# design.net
KiCad netlist of a schematic drawn in Altium Designer
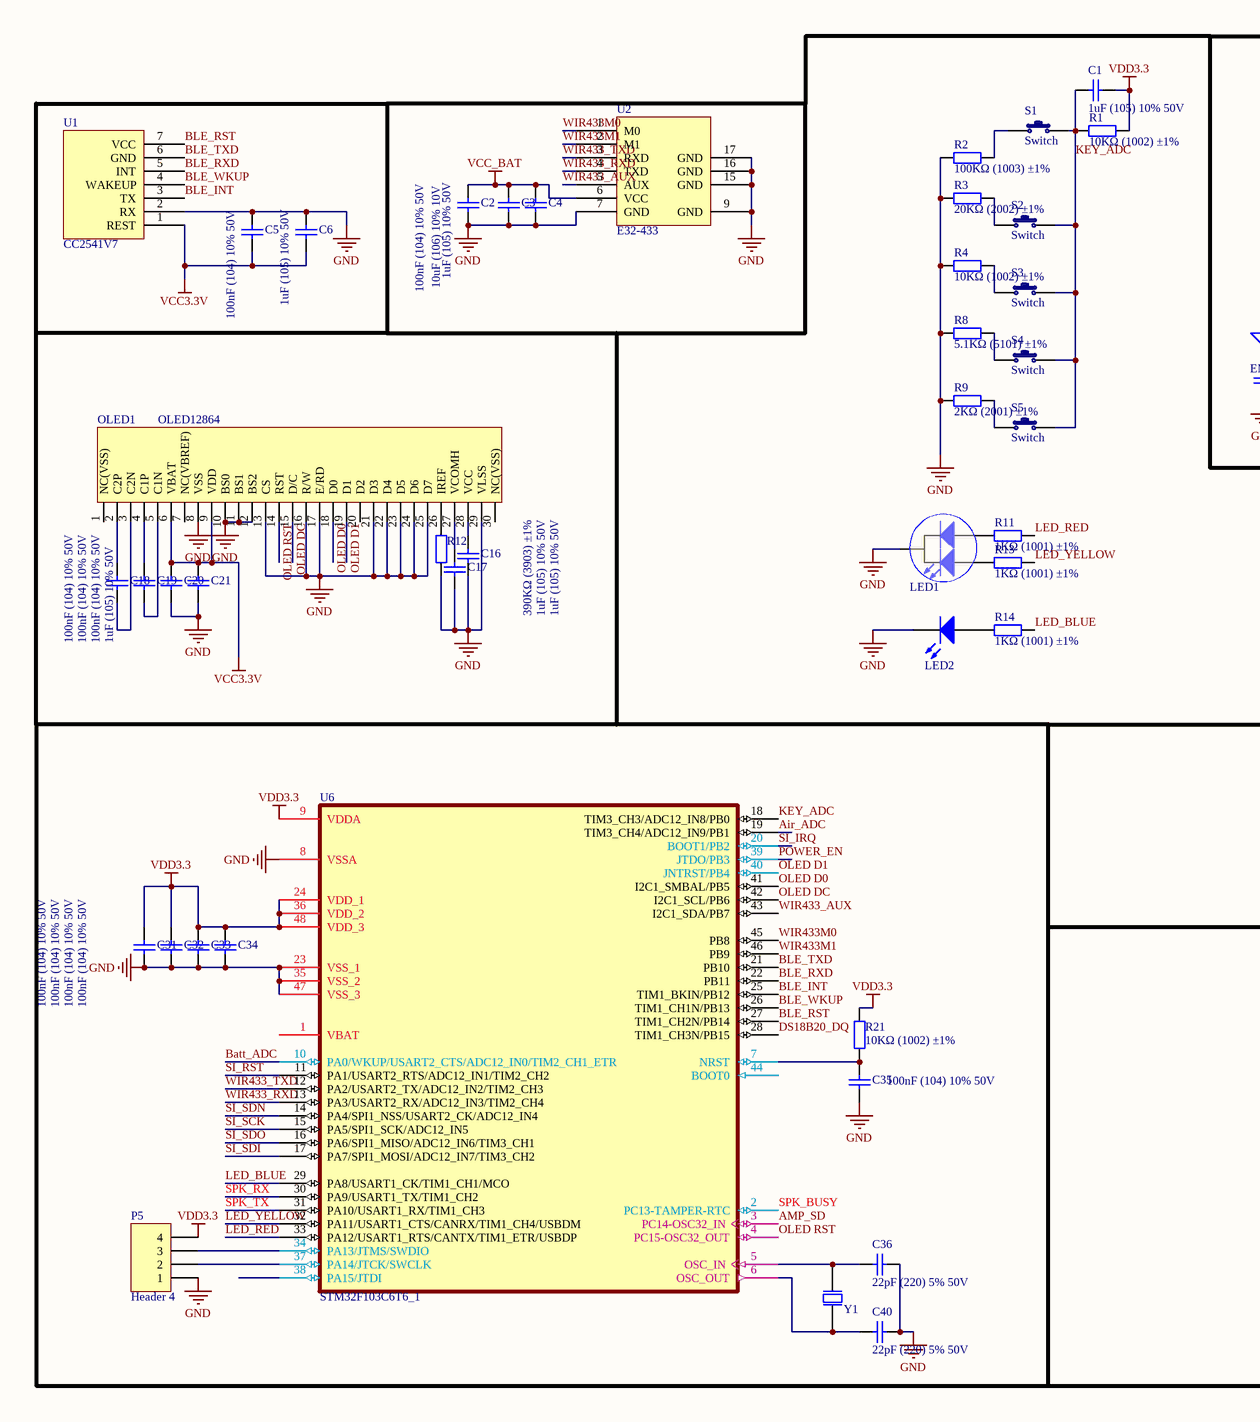
[diagram p0: 消防背表 备份.SchDoc, left]
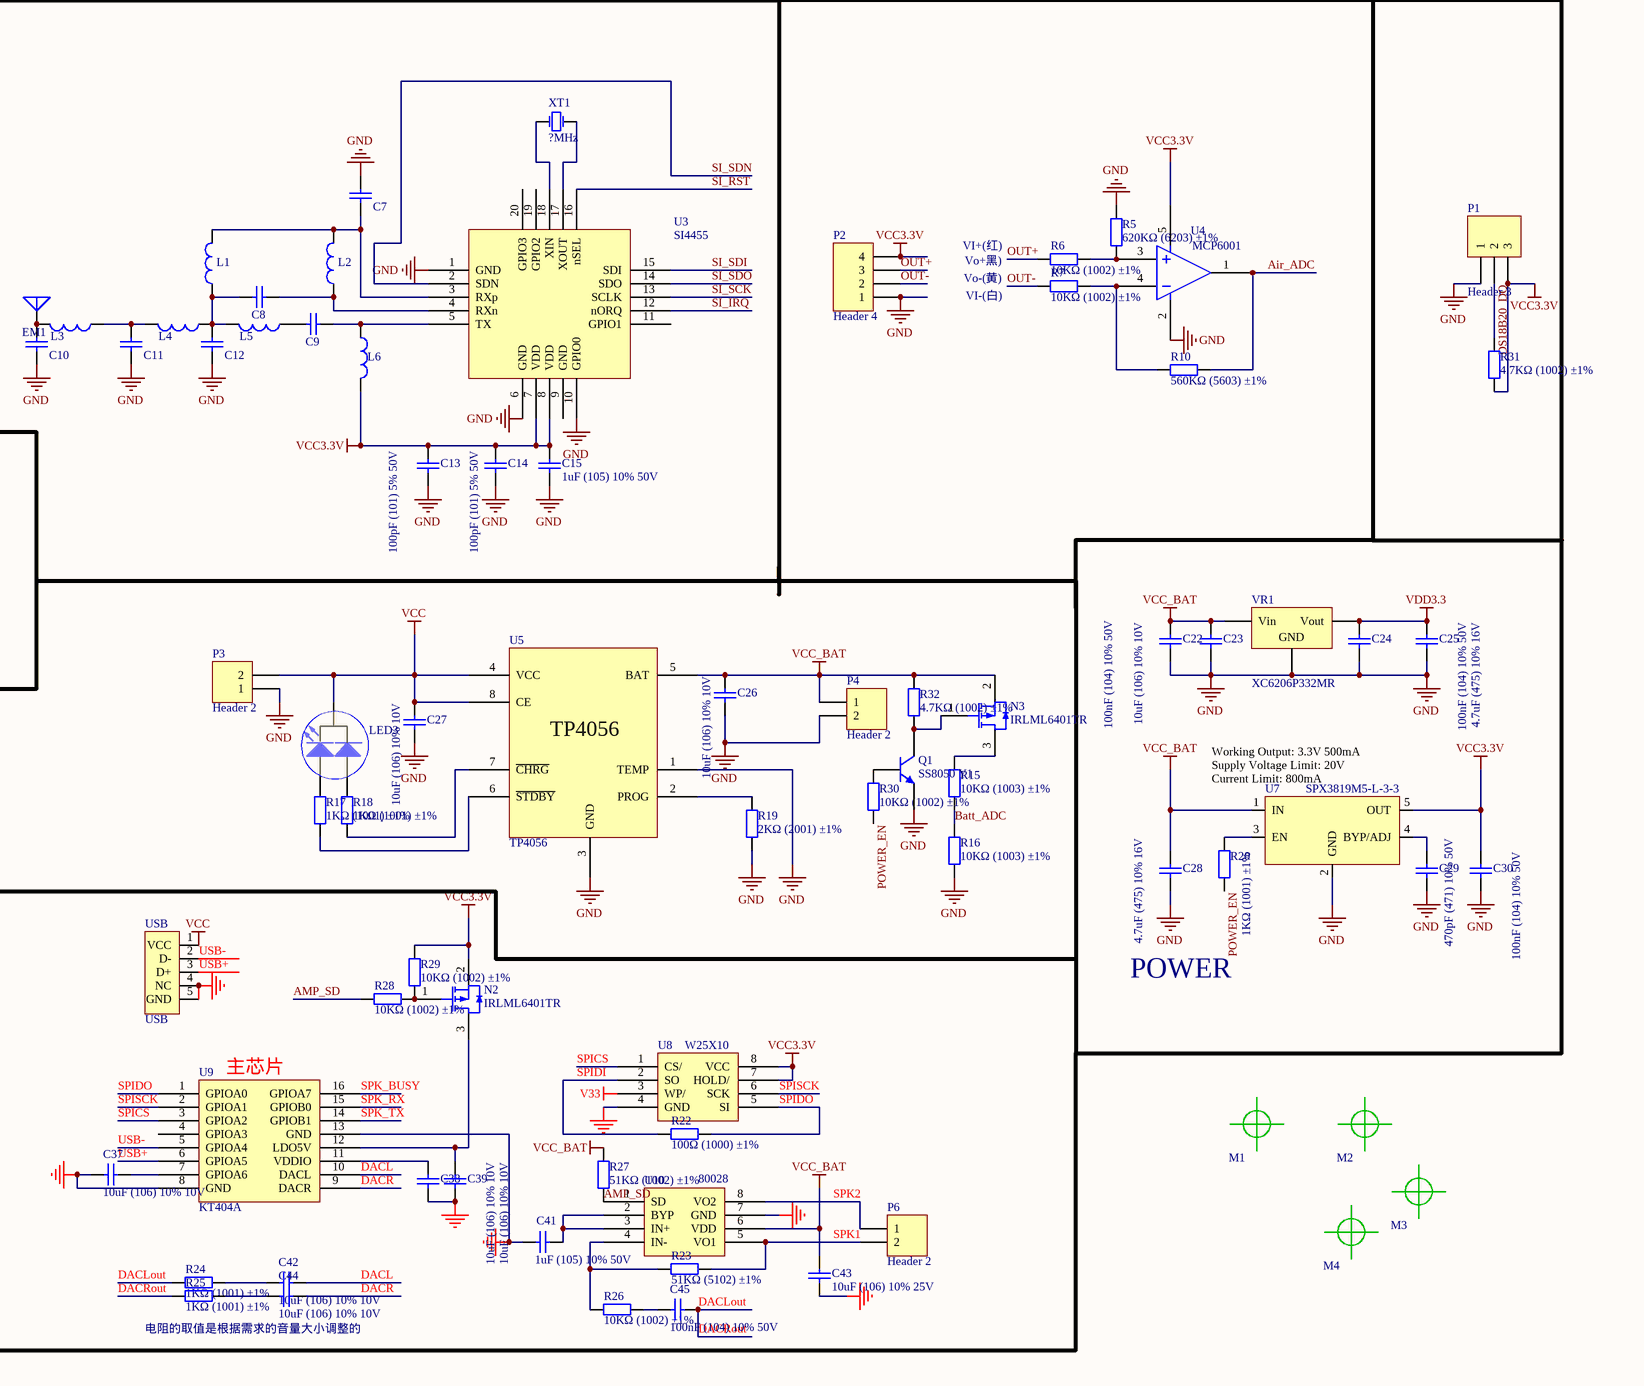
[diagram p1: 消防背表 备份.SchDoc, right]

(export (version "E")
  (design (tool "Eeschema 10.0.6"))
  (components
    (comp (ref "C1")
      (value "1uF (105) 10% 50V")
      (footprint "0603_C")
      (description "贴片电容")
      (libsource (lib "Miscellaneous Devices LC ") (part "0603 1uF (105) 10% 50V"))
    )
    (comp (ref "C2")
      (value "1uF (105) 10% 50V")
      (footprint "0603_C")
      (description "贴片电容")
      (libsource (lib "Miscellaneous Devices LC ") (part "0603 1uF (105) 10% 50V"))
    )
    (comp (ref "C3")
      (value "10uF (106) 10% 10V")
      (footprint "0603_C")
      (description "贴片电容")
      (libsource (lib "Miscellaneous Devices LC ") (part "0603 10uF (106) 10% 10V"))
    )
    (comp (ref "C4")
      (value "100nF (104) 10% 50V")
      (footprint "0603_C")
      (description "贴片电容")
      (libsource (lib "Miscellaneous Devices LC ") (part "0603 100nF (104) 10% 50V"))
    )
    (comp (ref "C5")
      (value "100nF (104) 10% 50V")
      (footprint "0603_C")
      (description "贴片电容")
      (libsource (lib "Miscellaneous Devices LC ") (part "0603 100nF (104) 10% 50V"))
    )
    (comp (ref "C6")
      (value "1uF (105) 10% 50V")
      (footprint "0603_C")
      (description "贴片电容")
      (libsource (lib "Miscellaneous Devices LC ") (part "0603 1uF (105) 10% 50V"))
    )
    (comp (ref "C7")
      (value "Cap Chip")
      (footprint "CAPC1608N")
      (description "Polarized Capacitor (Radial)")
      (fields (field (name "PUBLISHER") "Altium Limited"))
      (libsource (lib "(NEW)DRC_MD Library") (part "Cap Chip"))
    )
    (comp (ref "C8")
      (value "Cap Chip")
      (footprint "CAPC1608N")
      (description "Polarized Capacitor (Radial)")
      (fields (field (name "PUBLISHER") "Altium Limited"))
      (libsource (lib "(NEW)DRC_MD Library") (part "Cap Chip"))
    )
    (comp (ref "C9")
      (value "Cap Chip")
      (footprint "CAPC1608N")
      (description "Polarized Capacitor (Radial)")
      (fields (field (name "PUBLISHER") "Altium Limited"))
      (libsource (lib "(NEW)DRC_MD Library") (part "Cap Chip"))
    )
    (comp (ref "C10")
      (value "Cap Chip")
      (footprint "CAPC1608N")
      (description "Polarized Capacitor (Radial)")
      (fields (field (name "PUBLISHER") "Altium Limited"))
      (libsource (lib "(NEW)DRC_MD Library") (part "Cap Chip"))
    )
    (comp (ref "C11")
      (value "Cap Chip")
      (footprint "CAPC1608N")
      (description "Polarized Capacitor (Radial)")
      (fields (field (name "PUBLISHER") "Altium Limited"))
      (libsource (lib "(NEW)DRC_MD Library") (part "Cap Chip"))
    )
    (comp (ref "C12")
      (value "Cap Chip")
      (footprint "CAPC1608N")
      (description "Polarized Capacitor (Radial)")
      (fields (field (name "PUBLISHER") "Altium Limited"))
      (libsource (lib "(NEW)DRC_MD Library") (part "Cap Chip"))
    )
    (comp (ref "C13")
      (value "100pF (101) 5% 50V")
      (footprint "0603_C")
      (description "贴片电容")
      (libsource (lib "Miscellaneous Devices LC ") (part "0603 100pF (101) 5% 50V"))
    )
    (comp (ref "C14")
      (value "100pF (101) 5% 50V")
      (footprint "0603_C")
      (description "贴片电容")
      (libsource (lib "Miscellaneous Devices LC ") (part "0603 100pF (101) 5% 50V"))
    )
    (comp (ref "C15")
      (value "1uF (105) 10% 50V")
      (footprint "0603_C")
      (description "贴片电容")
      (libsource (lib "Miscellaneous Devices LC ") (part "0603 1uF (105) 10% 50V"))
    )
    (comp (ref "C16")
      (value "1uF (105) 10% 50V")
      (footprint "0603_C")
      (description "贴片电容")
      (libsource (lib "Miscellaneous Devices LC ") (part "0603 1uF (105) 10% 50V"))
    )
    (comp (ref "C17")
      (value "1uF (105) 10% 50V")
      (footprint "0603_C")
      (description "贴片电容")
      (libsource (lib "Miscellaneous Devices LC ") (part "0603 1uF (105) 10% 50V"))
    )
    (comp (ref "C18")
      (value "100nF (104) 10% 50V")
      (footprint "0603_C")
      (description "贴片电容")
      (libsource (lib "Miscellaneous Devices LC ") (part "0603 100nF (104) 10% 50V"))
    )
    (comp (ref "C19")
      (value "100nF (104) 10% 50V")
      (footprint "0603_C")
      (description "贴片电容")
      (libsource (lib "Miscellaneous Devices LC ") (part "0603 100nF (104) 10% 50V"))
    )
    (comp (ref "C20")
      (value "100nF (104) 10% 50V")
      (footprint "0603_C")
      (description "贴片电容")
      (libsource (lib "Miscellaneous Devices LC ") (part "0603 100nF (104) 10% 50V"))
    )
    (comp (ref "C21")
      (value "1uF (105) 10% 50V")
      (footprint "0603_C")
      (description "贴片电容")
      (libsource (lib "Miscellaneous Devices LC ") (part "0603 1uF (105) 10% 50V"))
    )
    (comp (ref "C22")
      (value "100nF (104) 10% 50V")
      (footprint "0603_C")
      (description "贴片电容")
      (libsource (lib "Miscellaneous Devices LC ") (part "0603 100nF (104) 10% 50V"))
    )
    (comp (ref "C23")
      (value "10uF (106) 10% 10V")
      (footprint "0603_C")
      (description "贴片电容")
      (libsource (lib "Miscellaneous Devices LC ") (part "0603 10uF (106) 10% 10V"))
    )
    (comp (ref "C24")
      (value "4.7uF (475) 10% 16V")
      (footprint "0603_C")
      (description "贴片电容")
      (libsource (lib "Miscellaneous Devices LC ") (part "0603 4.7uF (475) 10% 16V"))
    )
    (comp (ref "C25")
      (value "100nF (104) 10% 50V")
      (footprint "0603_C")
      (description "贴片电容")
      (libsource (lib "Miscellaneous Devices LC ") (part "0603 100nF (104) 10% 50V"))
    )
    (comp (ref "C26")
      (value "10uF (106) 10% 10V")
      (footprint "0603_C")
      (description "贴片电容")
      (libsource (lib "Miscellaneous Devices LC ") (part "0603 10uF (106) 10% 10V"))
    )
    (comp (ref "C27")
      (value "10uF (106) 10% 10V")
      (footprint "0603_C")
      (description "贴片电容")
      (libsource (lib "Miscellaneous Devices LC ") (part "0603 10uF (106) 10% 10V"))
    )
    (comp (ref "C28")
      (value "4.7uF (475) 10% 16V")
      (footprint "0603_C")
      (description "贴片电容")
      (libsource (lib "Miscellaneous Devices LC ") (part "0603 4.7uF (475) 10% 16V"))
    )
    (comp (ref "C29")
      (value "470pF (471) 10% 50V")
      (footprint "0603_C")
      (description "贴片电容")
      (libsource (lib "Miscellaneous Devices LC ") (part "0603 470pF (471) 10% 50V"))
    )
    (comp (ref "C30")
      (value "100nF (104) 10% 50V")
      (footprint "0603_C")
      (description "贴片电容")
      (libsource (lib "Miscellaneous Devices LC ") (part "0603 100nF (104) 10% 50V"))
    )
    (comp (ref "C31")
      (value "100nF (104) 10% 50V")
      (footprint "0603_C")
      (description "贴片电容")
      (libsource (lib "Miscellaneous Devices LC ") (part "0603 100nF (104) 10% 50V"))
    )
    (comp (ref "C32")
      (value "100nF (104) 10% 50V")
      (footprint "0603_C")
      (description "贴片电容")
      (libsource (lib "Miscellaneous Devices LC ") (part "0603 100nF (104) 10% 50V"))
    )
    (comp (ref "C33")
      (value "100nF (104) 10% 50V")
      (footprint "0603_C")
      (description "贴片电容")
      (libsource (lib "Miscellaneous Devices LC ") (part "0603 100nF (104) 10% 50V"))
    )
    (comp (ref "C34")
      (value "100nF (104) 10% 50V")
      (footprint "0603_C")
      (description "贴片电容")
      (libsource (lib "Miscellaneous Devices LC ") (part "0603 100nF (104) 10% 50V"))
    )
    (comp (ref "C35")
      (value "100nF (104) 10% 50V")
      (footprint "0603_C")
      (description "贴片电容")
      (libsource (lib "Miscellaneous Devices LC ") (part "0603 100nF (104) 10% 50V"))
    )
    (comp (ref "C36")
      (value "22pF (220) 5% 50V")
      (footprint "0603_C")
      (description "贴片电容")
      (libsource (lib "Miscellaneous Devices LC ") (part "0603 22pF (220) 5% 50V"))
    )
    (comp (ref "C37")
      (value "10uF (106) 10% 10V")
      (footprint "0603_C")
      (description "贴片电容")
      (libsource (lib "Miscellaneous Devices LC ") (part "0603 10uF (106) 10% 10V"))
    )
    (comp (ref "C38")
      (value "10uF (106) 10% 10V")
      (footprint "0603_C")
      (description "贴片电容")
      (libsource (lib "Miscellaneous Devices LC ") (part "0603 10uF (106) 10% 10V"))
    )
    (comp (ref "C39")
      (value "10uF (106) 10% 10V")
      (footprint "0603_C")
      (description "贴片电容")
      (libsource (lib "Miscellaneous Devices LC ") (part "0603 10uF (106) 10% 10V"))
    )
    (comp (ref "C40")
      (value "22pF (220) 5% 50V")
      (footprint "0603_C")
      (description "贴片电容")
      (libsource (lib "Miscellaneous Devices LC ") (part "0603 22pF (220) 5% 50V"))
    )
    (comp (ref "C41")
      (value "1uF (105) 10% 50V")
      (footprint "0603_C")
      (description "贴片电容")
      (libsource (lib "Miscellaneous Devices LC ") (part "0603 1uF (105) 10% 50V"))
    )
    (comp (ref "C42")
      (value "10uF (106) 10% 10V")
      (footprint "0603_C")
      (description "贴片电容")
      (libsource (lib "Miscellaneous Devices LC ") (part "0603 10uF (106) 10% 10V"))
    )
    (comp (ref "C43")
      (value "10uF (106) 10% 25V")
      (footprint "0805_C")
      (description "贴片电容")
      (libsource (lib "Miscellaneous Devices LC ") (part "0805 10uF (106) 10% 25V"))
    )
    (comp (ref "C44")
      (value "10uF (106) 10% 10V")
      (footprint "0603_C")
      (description "贴片电容")
      (libsource (lib "Miscellaneous Devices LC ") (part "0603 10uF (106) 10% 10V"))
    )
    (comp (ref "C45")
      (value "100nF (104) 10% 50V")
      (footprint "0603_C")
      (description "贴片电容")
      (libsource (lib "Miscellaneous Devices LC ") (part "0603 100nF (104) 10% 50V"))
    )
    (comp (ref "EM1")
      (value "Ant_2.4G")
      (footprint "ANT_2.4G")
      (description "Antenna")
      (libsource (lib "Integrated_Library") (part "Ant_2.4G"))
    )
    (comp (ref "L1")
      (value "Inductor Chip")
      (footprint "CR1608-0603")
      (description "Inductor")
      (fields (field (name "PUBLISHER") "Altium Limited"))
      (libsource (lib "(NEW)DRC_MD Library") (part "Inductor Chip"))
    )
    (comp (ref "L2")
      (value "Inductor Chip")
      (footprint "CR1608-0603")
      (description "Inductor")
      (fields (field (name "PUBLISHER") "Altium Limited"))
      (libsource (lib "(NEW)DRC_MD Library") (part "Inductor Chip"))
    )
    (comp (ref "L3")
      (value "Inductor Chip")
      (footprint "CR1608-0603")
      (description "Inductor")
      (fields (field (name "PUBLISHER") "Altium Limited"))
      (libsource (lib "(NEW)DRC_MD Library") (part "Inductor Chip"))
    )
    (comp (ref "L4")
      (value "Inductor Chip")
      (footprint "CR1608-0603")
      (description "Inductor")
      (fields (field (name "PUBLISHER") "Altium Limited"))
      (libsource (lib "(NEW)DRC_MD Library") (part "Inductor Chip"))
    )
    (comp (ref "L5")
      (value "Inductor Chip")
      (footprint "CR1608-0603")
      (description "Inductor")
      (fields (field (name "PUBLISHER") "Altium Limited"))
      (libsource (lib "(NEW)DRC_MD Library") (part "Inductor Chip"))
    )
    (comp (ref "L6")
      (value "Inductor Chip")
      (footprint "CR1608-0603")
      (description "Inductor")
      (fields (field (name "PUBLISHER") "Altium Limited"))
      (libsource (lib "(NEW)DRC_MD Library") (part "Inductor Chip"))
    )
    (comp (ref "LED1")
      (value "LED-3-DOUBLE")
      (footprint "LED-R3-H5-DOUBLE")
      (description "Typical INFRARED GaAs LED")
      (fields (field (name "PUBLISHER") "Altium Limited"))
      (libsource (lib "(NEW)DRC_MD Library") (part "LED-3-DOUBLE"))
    )
    (comp (ref "LED2")
      (value "LED Chip")
      (footprint "CLED1608-0603")
      (description "Typical Chip LED")
      (fields (field (name "PUBLISHER") "Altium Limited"))
      (libsource (lib "(NEW)DRC_MD Library") (part "LED Chip"))
    )
    (comp (ref "LED3")
      (value "LED-3-DOUBLE")
      (footprint "LED-R3-H5-DOUBLE")
      (description "Typical INFRARED GaAs LED")
      (fields (field (name "PUBLISHER") "Altium Limited"))
      (libsource (lib "(NEW)DRC_MD Library") (part "LED-3-DOUBLE"))
    )
    (comp (ref "M1")
      (value "Screw Hole")
      (footprint "Screw hexagon 3mm")
      (libsource (lib "(NEW)DRC_MD Library") (part "Screw Hole"))
    )
    (comp (ref "M2")
      (value "Screw Hole")
      (footprint "Screw hexagon 3mm")
      (libsource (lib "(NEW)DRC_MD Library") (part "Screw Hole"))
    )
    (comp (ref "M3")
      (value "Screw Hole")
      (footprint "Screw hexagon 3mm")
      (libsource (lib "(NEW)DRC_MD Library") (part "Screw Hole"))
    )
    (comp (ref "M4")
      (value "Screw Hole")
      (footprint "Screw hexagon 3mm")
      (libsource (lib "(NEW)DRC_MD Library") (part "Screw Hole"))
    )
    (comp (ref "N2")
      (value "IRLML6401TR")
      (footprint "SOT23-3")
      (fields (field (name "Comment") "P-MOS"))
      (libsource (lib "kooloo_V1.0") (part "P-MOS"))
    )
    (comp (ref "N3")
      (value "IRLML6401TR")
      (footprint "SOT23-3")
      (fields (field (name "Comment") "P-MOS"))
      (libsource (lib "kooloo_V1.0") (part "P-MOS"))
    )
    (comp (ref "OLED1")
      (value "OLED12864")
      (footprint "OLED_0.96")
      (libsource (lib "封装库整理") (part "OLED12864"))
    )
    (comp (ref "P1")
      (value "Header 3")
      (footprint "HX2.54-3")
      (description "Header, 3-Pin")
      (fields (field (name "PUBLISHER") "Altium Limited"))
      (libsource (lib "(NEW)DRC_MD Library") (part "Header 3"))
    )
    (comp (ref "P2")
      (value "Header 4")
      (footprint "HX2.54-4")
      (description "Header, 4-Pin")
      (fields (field (name "PUBLISHER") "Altium Limited"))
      (libsource (lib "(NEW)DRC_MD Library") (part "Header 4"))
    )
    (comp (ref "P3")
      (value "Header 2")
      (footprint "HDR1X2")
      (description "Header, 2-Pin")
      (fields (field (name "PUBLISHER") "Altium Limited"))
      (libsource (lib "") (part "Header 2_1"))
    )
    (comp (ref "P4")
      (value "Header 2")
      (footprint "MOLEX 35363-0250")
      (description "Header, 2-Pin")
      (fields (field (name "PUBLISHER") "Altium Limited"))
      (libsource (lib "(NEW)DRC_MD Library") (part "Header 2"))
    )
    (comp (ref "P5")
      (value "Header 4")
      (footprint "HDR1X4")
      (description "Header, 4-Pin")
      (fields (field (name "PUBLISHER") "Altium Limited"))
      (libsource (lib "(NEW)DRC_MD Library") (part "Header 4"))
    )
    (comp (ref "P6")
      (value "Header 2")
      (footprint "HDR1X2")
      (description "Header, 2-Pin")
      (fields (field (name "PUBLISHER") "Altium Limited"))
      (libsource (lib "(NEW)DRC_MD Library") (part "Header 2"))
    )
    (comp (ref "Q1")
      (value "SS8050 Y1")
      (footprint "SOT-23(SOT-23-3)")
      (description "三极管")
      (libsource (lib "Miscellaneous Devices LC ") (part "SOT-23 SS8050 Y1"))
    )
    (comp (ref "R1")
      (value "10KΩ (1002) ±1%")
      (footprint "0603_R")
      (description "贴片电阻")
      (libsource (lib "Miscellaneous Devices LC ") (part "0603 10KΩ (1002) 1%"))
    )
    (comp (ref "R2")
      (value "100KΩ (1003) ±1%")
      (footprint "0603_R")
      (description "贴片电阻")
      (libsource (lib "") (part "0603 100KΩ (1003) 1%_1"))
    )
    (comp (ref "R3")
      (value "20KΩ (2002) ±1%")
      (footprint "0603_R")
      (description "贴片电阻")
      (libsource (lib "Miscellaneous Devices LC ") (part "0603 20KΩ (2002) 1%"))
    )
    (comp (ref "R4")
      (value "10KΩ (1002) ±1%")
      (footprint "0603_R")
      (description "贴片电阻")
      (libsource (lib "Miscellaneous Devices LC ") (part "0603 10KΩ (1002) 1%"))
    )
    (comp (ref "R5")
      (value "620KΩ (6203) ±1%")
      (footprint "0603_R")
      (description "贴片电阻")
      (libsource (lib "Miscellaneous Devices LC ") (part "0603 620KΩ (6203) 1%"))
    )
    (comp (ref "R6")
      (value "10KΩ (1002) ±1%")
      (footprint "0603_R")
      (description "贴片电阻")
      (libsource (lib "Miscellaneous Devices LC ") (part "0603 10KΩ (1002) 1%"))
    )
    (comp (ref "R7")
      (value "10KΩ (1002) ±1%")
      (footprint "0603_R")
      (description "贴片电阻")
      (libsource (lib "Miscellaneous Devices LC ") (part "0603 10KΩ (1002) 1%"))
    )
    (comp (ref "R8")
      (value "5.1KΩ (5101) ±1%")
      (footprint "0603_R")
      (description "贴片电阻")
      (libsource (lib "Miscellaneous Devices LC ") (part "0603 5.1KΩ (5101) 1%"))
    )
    (comp (ref "R9")
      (value "2KΩ (2001) ±1%")
      (footprint "0603_R")
      (description "贴片电阻")
      (libsource (lib "") (part "0603 2KΩ (2001) 1%_1"))
    )
    (comp (ref "R10")
      (value "560KΩ (5603) ±1%")
      (footprint "0603_R")
      (description "贴片电阻")
      (libsource (lib "Miscellaneous Devices LC ") (part "0603 560KΩ (5603) 1%"))
    )
    (comp (ref "R11")
      (value "1KΩ (1001) ±1%")
      (footprint "0603_R")
      (description "贴片电阻")
      (libsource (lib "Miscellaneous Devices LC ") (part "0603 1KΩ (1001) 1%"))
    )
    (comp (ref "R12")
      (value "390KΩ (3903) ±1%")
      (footprint "0603_R")
      (description "贴片电阻")
      (libsource (lib "Miscellaneous Devices LC ") (part "0603 390KΩ (3903) 1%"))
    )
    (comp (ref "R13")
      (value "1KΩ (1001) ±1%")
      (footprint "0603_R")
      (description "贴片电阻")
      (libsource (lib "Miscellaneous Devices LC ") (part "0603 1KΩ (1001) 1%"))
    )
    (comp (ref "R14")
      (value "1KΩ (1001) ±1%")
      (footprint "0603_R")
      (description "贴片电阻")
      (libsource (lib "Miscellaneous Devices LC ") (part "0603 1KΩ (1001) 1%"))
    )
    (comp (ref "R15")
      (value "10KΩ (1003) ±1%")
      (footprint "0603_R")
      (description "贴片电阻")
      (libsource (lib "Miscellaneous Devices LC ") (part "0603 100KΩ (1003) 1%"))
    )
    (comp (ref "R16")
      (value "10KΩ (1003) ±1%")
      (footprint "0603_R")
      (description "贴片电阻")
      (libsource (lib "Miscellaneous Devices LC ") (part "0603 100KΩ (1003) 1%"))
    )
    (comp (ref "R17")
      (value "1KΩ (1001) ±1%")
      (footprint "0603_R")
      (description "贴片电阻")
      (libsource (lib "") (part "0603 1KΩ (1001) 1%_1"))
    )
    (comp (ref "R18")
      (value "1KΩ (1001) ±1%")
      (footprint "0603_R")
      (description "贴片电阻")
      (libsource (lib "") (part "0603 1KΩ (1001) 1%_1"))
    )
    (comp (ref "R19")
      (value "2KΩ (2001) ±1%")
      (footprint "0603_R")
      (description "贴片电阻")
      (libsource (lib "Miscellaneous Devices LC ") (part "0603 2KΩ (2001) 1%"))
    )
    (comp (ref "R20")
      (value "1KΩ (1001) ±1%")
      (footprint "0603_R")
      (description "贴片电阻")
      (libsource (lib "") (part "0603 1KΩ (1001) 1%_2"))
    )
    (comp (ref "R21")
      (value "10KΩ (1002) ±1%")
      (footprint "0603_R")
      (description "贴片电阻")
      (libsource (lib "") (part "0603 10KΩ (1002) 1%_1"))
    )
    (comp (ref "R22")
      (value "100Ω (1000) ±1%")
      (footprint "0603_R")
      (description "贴片电阻")
      (libsource (lib "Miscellaneous Devices LC ") (part "0603 100Ω (1000) 1%"))
    )
    (comp (ref "R23")
      (value "51KΩ (5102) ±1%")
      (footprint "0603_R")
      (description "贴片电阻")
      (libsource (lib "Miscellaneous Devices LC ") (part "0603 51KΩ (5102) 1%"))
    )
    (comp (ref "R24")
      (value "1KΩ (1001) ±1%")
      (footprint "0603_R")
      (description "贴片电阻")
      (libsource (lib "Miscellaneous Devices LC ") (part "0603 1KΩ (1001) 1%"))
    )
    (comp (ref "R25")
      (value "1KΩ (1001) ±1%")
      (footprint "0603_R")
      (description "贴片电阻")
      (libsource (lib "Miscellaneous Devices LC ") (part "0603 1KΩ (1001) 1%"))
    )
    (comp (ref "R26")
      (value "10KΩ (1002) ±1%")
      (footprint "0603_R")
      (description "贴片电阻")
      (libsource (lib "Miscellaneous Devices LC ") (part "0603 10KΩ (1002) 1%"))
    )
    (comp (ref "R27")
      (value "51KΩ (1002) ±1%")
      (footprint "0603_R")
      (description "贴片电阻")
      (libsource (lib "") (part "0603 10KΩ (1002) 1%_1"))
    )
    (comp (ref "R28")
      (value "10KΩ (1002) ±1%")
      (footprint "0603_R")
      (description "贴片电阻")
      (libsource (lib "") (part "0603 10KΩ (1002) 1%_2"))
    )
    (comp (ref "R29")
      (value "10KΩ (1002) ±1%")
      (footprint "0603_R")
      (description "贴片电阻")
      (libsource (lib "") (part "0603 10KΩ (1002) 1%_3"))
    )
    (comp (ref "R30")
      (value "10KΩ (1002) ±1%")
      (footprint "0603_R")
      (description "贴片电阻")
      (libsource (lib "") (part "0603 10KΩ (1002) 1%_3"))
    )
    (comp (ref "R31")
      (value "4.7KΩ (1002) ±1%")
      (footprint "0603_R")
      (description "贴片电阻")
      (libsource (lib "") (part "0603 10KΩ (1002) 1%_3"))
    )
    (comp (ref "R32")
      (value "4.7KΩ (1002) ±1%")
      (footprint "0603_R")
      (description "贴片电阻")
      (libsource (lib "") (part "0603 10KΩ (1002) 1%_3"))
    )
    (comp (ref "S1") (value "Switch") (footprint "Switch1") (libsource (lib "Common Device") (part "Switch")))
    (comp (ref "S2") (value "Switch") (footprint "Switch1") (libsource (lib "Common Device") (part "Switch")))
    (comp (ref "S3") (value "Switch") (footprint "Switch1") (libsource (lib "Common Device") (part "Switch")))
    (comp (ref "S4") (value "Switch") (footprint "Switch1") (libsource (lib "Common Device") (part "Switch")))
    (comp (ref "S5") (value "Switch") (footprint "Switch1") (libsource (lib "Common Device") (part "Switch")))
    (comp (ref "U1") (value "CC2541V7") (footprint "BLE_CC2451") (libsource (lib "si4455") (part "CC2541V7")))
    (comp (ref "U2") (value "E32-433") (footprint "E32_433") (libsource (lib "si4455") (part "E32-433")))
    (comp (ref "U3")
      (value "SI4455")
      (footprint "QFN50P300X300X80-20N")
      (libsource (lib "si4455") (part "SI4455"))
    )
    (comp (ref "U4") (value "MCP6001") (footprint "SOT23-5") (libsource (lib "kooloo_V1.0") (part "MCP6001")))
    (comp (ref "U5") (value "TP4056") (footprint "SOP-8_150mil") (libsource (lib "shenj") (part "TP4056")))
    (comp (ref "U6")
      (value "STM32F103C6T6_1")
      (footprint "LQFP-48")
      (description "STM32 ARM-based 32-bit MCU with 32 Kbytes Flash, 48-pin LQFP, Industrial Temperature")
      (fields (field (name "PUBLISHER") "*"))
      (libsource (lib "元件库") (part "STM32F103C6T6_1"))
    )
    (comp (ref "U7")
      (value "SPX3819M5-L-3-3")
      (footprint "SOT-23-6")
      (description "500mA, Low-Noise LDO Voltage Regulator")
      (libsource (lib "Vowstar_IC_General") (part "SPX3819"))
    )
    (comp (ref "U8") (value "W25X10") (footprint "SOIC127P790X265-8N") (libsource (lib "*") (part "W25X10")))
    (comp (ref "U9") (value "KT404A") (footprint "SOP-16M") (libsource (lib "*") (part "KT404A")))
    (comp (ref "U10") (value "80028") (footprint "SOP-8_150mil") (libsource (lib "*") (part "80028")))
    (comp (ref "USB")
      (value "USB")
      (footprint "USB-MICRO-B")
      (libsource (lib "(NEW)DRC_MD Library") (part "USB5"))
    )
    (comp (ref "VR1")
      (value "XC6206P332MR")
      (footprint "SOT-23-3L")
      (description "低压差线性稳压(LDO)")
      (libsource (lib "Miscellaneous Devices LC ") (part "SOT-23 XC6206P332MR"))
    )
    (comp (ref "XT1")
      (value "?MHz")
      (footprint "XTAL_5032")
      (description "Crystal Oscillator")
      (fields (field (name "Comment") "XTAL_5032") (field (name "PUBLISHER") "Altium Limited"))
      (libsource (lib "Integrated_Library") (part "XTAL_5032"))
    )
    (comp (ref "Y1")
      (value "XTAL")
      (footprint "XTAL-SMD")
      (description "Crystal Oscillator")
      (fields (field (name "PUBLISHER") "Altium Limited"))
      (libsource (lib "(NEW)DRC_MD Library") (part "XTAL"))
    )
  )
  (nets
    (net (code "1") (name "/AMP_SD") (class "Default")
      (node (ref "R27") (pin "1") (pinfunction "1_1") (pintype "passive"))
      (node (ref "R28") (pin "2") (pinfunction "2_2") (pintype "passive"))
      (node (ref "U10") (pin "1") (pinfunction "SD_1") (pintype "passive"))
      (node (ref "U6") (pin "3") (pinfunction "PC14-OSC32_IN_3") (pintype "bidirectional"))
    )
    (net (code "2") (name "/Air_ADC") (class "Default")
      (node (ref "R10") (pin "2") (pinfunction "2_2") (pintype "passive"))
      (node (ref "U4") (pin "1") (pintype "passive"))
      (node (ref "U6") (pin "19") (pinfunction "TIM3_CH4/ADC12_IN9/PB1_19") (pintype "bidirectional"))
    )
    (net (code "3") (name "/BLE_INT") (class "Default")
      (node (ref "U1") (pin "3") (pinfunction "TX_3") (pintype "passive"))
      (node (ref "U6") (pin "25") (pinfunction "TIM1_BKIN/PB12_25") (pintype "bidirectional"))
    )
    (net (code "4") (name "/BLE_RST") (class "Default")
      (node (ref "U1") (pin "7") (pinfunction "VCC_7") (pintype "passive"))
      (node (ref "U6") (pin "27") (pinfunction "TIM1_CH2N/PB14_27") (pintype "bidirectional"))
    )
    (net (code "5") (name "/BLE_RXD") (class "Default")
      (node (ref "U1") (pin "5") (pinfunction "INT_5") (pintype "passive"))
      (node (ref "U6") (pin "22") (pinfunction "PB11_22") (pintype "bidirectional"))
    )
    (net (code "6") (name "/BLE_TXD") (class "Default")
      (node (ref "U1") (pin "6") (pinfunction "GND_6") (pintype "passive"))
      (node (ref "U6") (pin "21") (pinfunction "PB10_21") (pintype "bidirectional"))
    )
    (net (code "7") (name "/BLE_WKUP") (class "Default")
      (node (ref "U1") (pin "4") (pinfunction "WAKEUP_4") (pintype "passive"))
      (node (ref "U6") (pin "26") (pinfunction "TIM1_CH1N/PB13_26") (pintype "bidirectional"))
    )
    (net (code "8") (name "/Batt_ADC") (class "Default")
      (node (ref "R15") (pin "1") (pinfunction "1_1") (pintype "passive"))
      (node (ref "R16") (pin "2") (pinfunction "2_2") (pintype "passive"))
      (node (ref "U6") (pin "10") (pinfunction "PA0/WKUP/USART2_CTS/ADC12_IN0/TIM2_CH1_ETR_10") (pintype "bidirectional"))
    )
    (net (code "9") (name "/DACL") (class "Default")
      (node (ref "C42") (pin "1") (pinfunction "1_1") (pintype "passive"))
      (node (ref "U9") (pin "10") (pinfunction "DACL_10") (pintype "passive"))
    )
    (net (code "10") (name "/DACLout") (class "Default")
      (node (ref "C45") (pin "1") (pinfunction "1_1") (pintype "passive"))
      (node (ref "R24") (pin "2") (pinfunction "2_2") (pintype "passive"))
      (node (ref "R25") (pin "2") (pinfunction "2_2") (pintype "passive"))
    )
    (net (code "11") (name "/DACR") (class "Default")
      (node (ref "C44") (pin "1") (pinfunction "1_1") (pintype "passive"))
      (node (ref "U9") (pin "9") (pinfunction "DACR_9") (pintype "passive"))
    )
    (net (code "12") (name "/DS18B20_DQ") (class "Default")
      (node (ref "P1") (pin "2") (pinfunction "2_2") (pintype "passive"))
      (node (ref "R31") (pin "1") (pinfunction "1_1") (pintype "passive"))
      (node (ref "U6") (pin "28") (pinfunction "TIM1_CH3N/PB15_28") (pintype "bidirectional"))
    )
    (net (code "13") (name "/KEY_ADC") (class "Default")
      (node (ref "C1") (pin "2") (pinfunction "2_2") (pintype "passive"))
      (node (ref "R1") (pin "1") (pinfunction "1_1") (pintype "passive"))
      (node (ref "S1") (pin "2") (pinfunction "1_2") (pintype "passive"))
      (node (ref "S2") (pin "2") (pinfunction "1_2") (pintype "passive"))
      (node (ref "S3") (pin "2") (pinfunction "1_2") (pintype "passive"))
      (node (ref "S4") (pin "2") (pinfunction "1_2") (pintype "passive"))
      (node (ref "S5") (pin "2") (pinfunction "1_2") (pintype "passive"))
      (node (ref "U6") (pin "18") (pinfunction "TIM3_CH3/ADC12_IN8/PB0_18") (pintype "bidirectional"))
    )
    (net (code "14") (name "/LED_BLUE") (class "Default")
      (node (ref "R14") (pin "1") (pinfunction "1_1") (pintype "passive"))
      (node (ref "U6") (pin "29") (pinfunction "PA8/USART1_CK/TIM1_CH1/MCO_29") (pintype "bidirectional"))
    )
    (net (code "15") (name "/LED_RED") (class "Default")
      (node (ref "R11") (pin "1") (pinfunction "1_1") (pintype "passive"))
      (node (ref "U6") (pin "33") (pinfunction "PA12/USART1_RTS/CANTX/TIM1_ETR/USBDP_33") (pintype "bidirectional"))
    )
    (net (code "16") (name "/LED_YELLOW") (class "Default")
      (node (ref "R13") (pin "1") (pinfunction "1_1") (pintype "passive"))
      (node (ref "U6") (pin "32") (pinfunction "PA11/USART1_CTS/CANRX/TIM1_CH4/USBDM_32") (pintype "bidirectional"))
    )
    (net (code "17") (name "/OLED D0") (class "Default")
      (node (ref "OLED1") (pin "18") (pinfunction "D0_18") (pintype "passive"))
      (node (ref "U6") (pin "41") (pinfunction "I2C1_SMBAL/PB5_41") (pintype "bidirectional"))
    )
    (net (code "18") (name "/OLED D1") (class "Default")
      (node (ref "OLED1") (pin "19") (pinfunction "D1_19") (pintype "passive"))
      (node (ref "U6") (pin "40") (pinfunction "JNTRST/PB4_40") (pintype "bidirectional"))
    )
    (net (code "19") (name "/OLED DC") (class "Default")
      (node (ref "OLED1") (pin "15") (pinfunction "D/C_15") (pintype "passive"))
      (node (ref "U6") (pin "42") (pinfunction "I2C1_SCL/PB6_42") (pintype "bidirectional"))
    )
    (net (code "20") (name "/OLED RST") (class "Default")
      (node (ref "OLED1") (pin "14") (pinfunction "RST_14") (pintype "passive"))
      (node (ref "U6") (pin "4") (pinfunction "PC15-OSC32_OUT_4") (pintype "bidirectional"))
    )
    (net (code "21") (name "/OUT+") (class "Default")
      (node (ref "P2") (pin "3") (pinfunction "3_3") (pintype "passive"))
      (node (ref "R6") (pin "1") (pinfunction "1_1") (pintype "passive"))
    )
    (net (code "22") (name "/OUT-") (class "Default")
      (node (ref "P2") (pin "2") (pinfunction "2_2") (pintype "passive"))
      (node (ref "R7") (pin "1") (pinfunction "1_1") (pintype "passive"))
    )
    (net (code "23") (name "/POWER_EN") (class "Default")
      (node (ref "R20") (pin "2") (pinfunction "2_2") (pintype "passive"))
      (node (ref "R30") (pin "2") (pinfunction "2_2") (pintype "passive"))
      (node (ref "U6") (pin "39") (pinfunction "JTDO/PB3_39") (pintype "bidirectional"))
    )
    (net (code "24") (name "/SI_IRQ") (class "Default")
      (node (ref "U3") (pin "12") (pinfunction "nORQ_12") (pintype "passive"))
      (node (ref "U6") (pin "20") (pinfunction "BOOT1/PB2_20") (pintype "bidirectional"))
    )
    (net (code "25") (name "/SI_RST") (class "Default")
      (node (ref "U3") (pin "16") (pinfunction "nSEL_16") (pintype "passive"))
      (node (ref "U6") (pin "11") (pinfunction "PA1/USART2_RTS/ADC12_IN1/TIM2_CH2_11") (pintype "bidirectional"))
    )
    (net (code "26") (name "/SI_SCK") (class "Default")
      (node (ref "U3") (pin "13") (pinfunction "SCLK_13") (pintype "passive"))
      (node (ref "U6") (pin "15") (pinfunction "PA5/SPI1_SCK/ADC12_IN5_15") (pintype "bidirectional"))
    )
    (net (code "27") (name "/SI_SDI") (class "Default")
      (node (ref "U3") (pin "15") (pinfunction "SDI_15") (pintype "passive"))
      (node (ref "U6") (pin "17") (pinfunction "PA7/SPI1_MOSI/ADC12_IN7/TIM3_CH2_17") (pintype "bidirectional"))
    )
    (net (code "28") (name "/SI_SDN") (class "Default")
      (node (ref "U3") (pin "2") (pinfunction "SDN_2") (pintype "passive"))
      (node (ref "U6") (pin "14") (pinfunction "PA4/SPI1_NSS/USART2_CK/ADC12_IN4_14") (pintype "bidirectional"))
    )
    (net (code "29") (name "/SI_SDO") (class "Default")
      (node (ref "U3") (pin "14") (pinfunction "SDO_14") (pintype "passive"))
      (node (ref "U6") (pin "16") (pinfunction "PA6/SPI1_MISO/ADC12_IN6/TIM3_CH1_16") (pintype "bidirectional"))
    )
    (net (code "30") (name "/SPICS") (class "Default")
      (node (ref "U8") (pin "1") (pinfunction "CS/_1") (pintype "passive"))
      (node (ref "U9") (pin "3") (pinfunction "GPIOA2_3") (pintype "passive"))
    )
    (net (code "31") (name "/SPIDI") (class "Default")
      (node (ref "R22") (pin "1") (pinfunction "1_1") (pintype "passive"))
      (node (ref "U8") (pin "2") (pinfunction "SO_2") (pintype "passive"))
    )
    (net (code "32") (name "/SPIDO") (class "Default")
      (node (ref "R22") (pin "2") (pinfunction "2_2") (pintype "passive"))
      (node (ref "U8") (pin "5") (pinfunction "SI_5") (pintype "passive"))
      (node (ref "U9") (pin "1") (pinfunction "GPIOA0_1") (pintype "passive"))
    )
    (net (code "33") (name "/SPISCK") (class "Default")
      (node (ref "U8") (pin "6") (pinfunction "SCK_6") (pintype "passive"))
      (node (ref "U9") (pin "2") (pinfunction "GPIOA1_2") (pintype "passive"))
    )
    (net (code "34") (name "/SPK1") (class "Default")
      (node (ref "P6") (pin "2") (pinfunction "2_2") (pintype "passive"))
      (node (ref "R23") (pin "2") (pinfunction "2_2") (pintype "passive"))
      (node (ref "U10") (pin "5") (pinfunction "VO1_5") (pintype "passive"))
    )
    (net (code "35") (name "/SPK2") (class "Default")
      (node (ref "P6") (pin "1") (pinfunction "1_1") (pintype "passive"))
      (node (ref "U10") (pin "8") (pinfunction "VO2_8") (pintype "passive"))
    )
    (net (code "36") (name "/SPK_BUSY") (class "Default")
      (node (ref "U6") (pin "2") (pinfunction "PC13-TAMPER-RTC_2") (pintype "bidirectional"))
      (node (ref "U9") (pin "16") (pinfunction "GPIOA7_16") (pintype "passive"))
    )
    (net (code "37") (name "/SPK_RX") (class "Default")
      (node (ref "U6") (pin "30") (pinfunction "PA9/USART1_TX/TIM1_CH2_30") (pintype "bidirectional"))
      (node (ref "U9") (pin "15") (pinfunction "GPIOB0_15") (pintype "passive"))
    )
    (net (code "38") (name "/SPK_TX") (class "Default")
      (node (ref "U6") (pin "31") (pinfunction "PA10/USART1_RX/TIM1_CH3_31") (pintype "bidirectional"))
      (node (ref "U9") (pin "14") (pinfunction "GPIOB1_14") (pintype "passive"))
    )
    (net (code "39") (name "/USB+") (class "Default")
      (node (ref "U9") (pin "6") (pinfunction "GPIOA5_6") (pintype "passive"))
      (node (ref "USB") (pin "3") (pinfunction "D+_3") (pintype "passive"))
    )
    (net (code "40") (name "/USB-") (class "Default")
      (node (ref "U9") (pin "5") (pinfunction "GPIOA4_5") (pintype "passive"))
      (node (ref "USB") (pin "2") (pinfunction "D-_2") (pintype "passive"))
    )
    (net (code "41") (name "/WIR433M0") (class "Default")
      (node (ref "U2") (pin "1") (pinfunction "M0_1") (pintype "passive"))
      (node (ref "U6") (pin "45") (pinfunction "PB8_45") (pintype "bidirectional"))
    )
    (net (code "42") (name "/WIR433M1") (class "Default")
      (node (ref "U2") (pin "2") (pinfunction "M1_2") (pintype "passive"))
      (node (ref "U6") (pin "46") (pinfunction "PB9_46") (pintype "bidirectional"))
    )
    (net (code "43") (name "/WIR433_AUX") (class "Default")
      (node (ref "U2") (pin "5") (pinfunction "AUX_5") (pintype "passive"))
      (node (ref "U6") (pin "43") (pinfunction "I2C1_SDA/PB7_43") (pintype "bidirectional"))
    )
    (net (code "44") (name "/WIR433_RXD") (class "Default")
      (node (ref "U2") (pin "4") (pinfunction "TXD_4") (pintype "passive"))
      (node (ref "U6") (pin "13") (pinfunction "PA3/USART2_RX/ADC12_IN3/TIM2_CH4_13") (pintype "bidirectional"))
    )
    (net (code "45") (name "/WIR433_TXD") (class "Default")
      (node (ref "U2") (pin "3") (pinfunction "RXD_3") (pintype "passive"))
      (node (ref "U6") (pin "12") (pinfunction "PA2/USART2_TX/ADC12_IN2/TIM2_CH3_12") (pintype "bidirectional"))
    )
    (net (code "46") (name "GND") (class "Default")
      (node (ref "C10") (pin "1") (pinfunction "1_1") (pintype "passive"))
      (node (ref "C11") (pin "1") (pinfunction "1_1") (pintype "passive"))
      (node (ref "C12") (pin "1") (pinfunction "1_1") (pintype "passive"))
      (node (ref "C13") (pin "2") (pinfunction "2_2") (pintype "passive"))
      (node (ref "C14") (pin "2") (pinfunction "2_2") (pintype "passive"))
      (node (ref "C15") (pin "1") (pinfunction "1_1") (pintype "passive"))
      (node (ref "C16") (pin "1") (pinfunction "1_1") (pintype "passive"))
      (node (ref "C17") (pin "1") (pinfunction "1_1") (pintype "passive"))
      (node (ref "C2") (pin "1") (pinfunction "1_1") (pintype "passive"))
      (node (ref "C20") (pin "1") (pinfunction "1_1") (pintype "passive"))
      (node (ref "C21") (pin "1") (pinfunction "1_1") (pintype "passive"))
      (node (ref "C22") (pin "1") (pinfunction "1_1") (pintype "passive"))
      (node (ref "C23") (pin "1") (pinfunction "1_1") (pintype "passive"))
      (node (ref "C24") (pin "1") (pinfunction "1_1") (pintype "passive"))
      (node (ref "C25") (pin "1") (pinfunction "1_1") (pintype "passive"))
      (node (ref "C26") (pin "1") (pinfunction "1_1") (pintype "passive"))
      (node (ref "C27") (pin "1") (pinfunction "1_1") (pintype "passive"))
      (node (ref "C28") (pin "1") (pinfunction "1_1") (pintype "passive"))
      (node (ref "C29") (pin "1") (pinfunction "1_1") (pintype "passive"))
      (node (ref "C3") (pin "1") (pinfunction "1_1") (pintype "passive"))
      (node (ref "C30") (pin "1") (pinfunction "1_1") (pintype "passive"))
      (node (ref "C31") (pin "1") (pinfunction "1_1") (pintype "passive"))
      (node (ref "C32") (pin "1") (pinfunction "1_1") (pintype "passive"))
      (node (ref "C33") (pin "1") (pinfunction "1_1") (pintype "passive"))
      (node (ref "C34") (pin "1") (pinfunction "1_1") (pintype "passive"))
      (node (ref "C35") (pin "1") (pinfunction "1_1") (pintype "passive"))
      (node (ref "C36") (pin "2") (pinfunction "2_2") (pintype "passive"))
      (node (ref "C37") (pin "2") (pinfunction "2_2") (pintype "passive"))
      (node (ref "C38") (pin "2") (pinfunction "2_2") (pintype "passive"))
      (node (ref "C39") (pin "2") (pinfunction "2_2") (pintype "passive"))
      (node (ref "C4") (pin "1") (pinfunction "1_1") (pintype "passive"))
      (node (ref "C40") (pin "2") (pinfunction "2_2") (pintype "passive"))
      (node (ref "C41") (pin "1") (pinfunction "1_1") (pintype "passive"))
      (node (ref "C43") (pin "1") (pinfunction "1_1") (pintype "passive"))
      (node (ref "C5") (pin "2") (pinfunction "2_2") (pintype "passive"))
      (node (ref "C6") (pin "2") (pinfunction "2_2") (pintype "passive"))
      (node (ref "C7") (pin "2") (pinfunction "2_2") (pintype "passive"))
      (node (ref "LED1") (pin "1") (pinfunction "K_1") (pintype "passive"))
      (node (ref "LED2") (pin "2") (pinfunction "K_2") (pintype "passive"))
      (node (ref "OLED1") (pin "10") (pinfunction "BS0_10") (pintype "passive"))
      (node (ref "OLED1") (pin "11") (pinfunction "BS1_11") (pintype "passive"))
      (node (ref "OLED1") (pin "12") (pinfunction "BS2_12") (pintype "passive"))
      (node (ref "OLED1") (pin "13") (pinfunction "CS_13") (pintype "passive"))
      (node (ref "OLED1") (pin "16") (pinfunction "R/W_16") (pintype "passive"))
      (node (ref "OLED1") (pin "17") (pinfunction "E/RD_17") (pintype "passive"))
      (node (ref "OLED1") (pin "21") (pinfunction "D3_21") (pintype "passive"))
      (node (ref "OLED1") (pin "22") (pinfunction "D4_22") (pintype "passive"))
      (node (ref "OLED1") (pin "23") (pinfunction "D5_23") (pintype "passive"))
      (node (ref "OLED1") (pin "24") (pinfunction "D6_24") (pintype "passive"))
      (node (ref "OLED1") (pin "25") (pinfunction "D7_25") (pintype "passive"))
      (node (ref "OLED1") (pin "29") (pinfunction "VLSS_29") (pintype "passive"))
      (node (ref "OLED1") (pin "8") (pinfunction "VSS_8") (pintype "passive"))
      (node (ref "P1") (pin "1") (pinfunction "1_1") (pintype "passive"))
      (node (ref "P2") (pin "1") (pinfunction "1_1") (pintype "passive"))
      (node (ref "P3") (pin "1") (pinfunction "1_1") (pintype "passive"))
      (node (ref "P4") (pin "2") (pinfunction "2_2") (pintype "passive"))
      (node (ref "P5") (pin "1") (pinfunction "1_1") (pintype "passive"))
      (node (ref "Q1") (pin "2") (pinfunction "E_2") (pintype "passive"))
      (node (ref "R12") (pin "1") (pinfunction "1_1") (pintype "passive"))
      (node (ref "R16") (pin "1") (pinfunction "1_1") (pintype "passive"))
      (node (ref "R19") (pin "1") (pinfunction "1_1") (pintype "passive"))
      (node (ref "R2") (pin "1") (pinfunction "1_1") (pintype "passive"))
      (node (ref "R3") (pin "1") (pinfunction "1_1") (pintype "passive"))
      (node (ref "R4") (pin "1") (pinfunction "1_1") (pintype "passive"))
      (node (ref "R5") (pin "2") (pinfunction "2_2") (pintype "passive"))
      (node (ref "R8") (pin "1") (pinfunction "1_1") (pintype "passive"))
      (node (ref "R9") (pin "1") (pinfunction "1_1") (pintype "passive"))
      (node (ref "U1") (pin "2") (pinfunction "RX_2") (pintype "passive"))
      (node (ref "U10") (pin "7") (pinfunction "GND_7") (pintype "passive"))
      (node (ref "U2") (pin "15") (pinfunction "GND_15") (pintype "passive"))
      (node (ref "U2") (pin "16") (pinfunction "GND_16") (pintype "passive"))
      (node (ref "U2") (pin "17") (pinfunction "GND_17") (pintype "passive"))
      (node (ref "U2") (pin "7") (pinfunction "GND_7") (pintype "passive"))
      (node (ref "U2") (pin "9") (pinfunction "GND_9") (pintype "passive"))
      (node (ref "U3") (pin "1") (pinfunction "GND_1") (pintype "passive"))
      (node (ref "U3") (pin "10") (pinfunction "GPIO0_10") (pintype "passive"))
      (node (ref "U3") (pin "6") (pinfunction "GND_6") (pintype "passive"))
      (node (ref "U4") (pin "2") (pintype "passive"))
      (node (ref "U5") (pin "1") (pinfunction "TEMP_1") (pintype "passive"))
      (node (ref "U5") (pin "3") (pinfunction "GND_3") (pintype "passive"))
      (node (ref "U6") (pin "23") (pinfunction "VSS_1_23") (pintype "power_in"))
      (node (ref "U6") (pin "35") (pinfunction "VSS_2_35") (pintype "power_in"))
      (node (ref "U6") (pin "47") (pinfunction "VSS_3_47") (pintype "power_in"))
      (node (ref "U6") (pin "8") (pinfunction "VSSA_8") (pintype "power_in"))
      (node (ref "U7") (pin "2") (pinfunction "GND_2") (pintype "passive"))
      (node (ref "U8") (pin "4") (pinfunction "GND_4") (pintype "passive"))
      (node (ref "U9") (pin "13") (pinfunction "GND_13") (pintype "passive"))
      (node (ref "U9") (pin "8") (pinfunction "GND_8") (pintype "passive"))
      (node (ref "USB") (pin "4") (pinfunction "NC_4") (pintype "passive"))
      (node (ref "USB") (pin "5") (pinfunction "GND_5") (pintype "passive"))
      (node (ref "VR1") (pin "1") (pinfunction "GND_1") (pintype "passive"))
    )
    (net (code "47") (name "Net-(C9-Pad2)") (class "Default")
      (node (ref "C9") (pin "2") (pinfunction "2_2") (pintype "passive"))
      (node (ref "L5") (pin "1") (pinfunction "1_1") (pintype "passive"))
    )
    (net (code "48") (name "Net-(C11-Pad2)") (class "Default")
      (node (ref "C11") (pin "2") (pinfunction "2_2") (pintype "passive"))
      (node (ref "L3") (pin "1") (pinfunction "1_1") (pintype "passive"))
      (node (ref "L4") (pin "2") (pinfunction "2_2") (pintype "passive"))
    )
    (net (code "49") (name "Net-(C12-Pad2)") (class "Default")
      (node (ref "C12") (pin "2") (pinfunction "2_2") (pintype "passive"))
      (node (ref "C8") (pin "2") (pinfunction "2_2") (pintype "passive"))
      (node (ref "L1") (pin "1") (pinfunction "1_1") (pintype "passive"))
      (node (ref "L4") (pin "1") (pinfunction "1_1") (pintype "passive"))
      (node (ref "L5") (pin "2") (pinfunction "2_2") (pintype "passive"))
    )
    (net (code "50") (name "Net-(C42-Pad2)") (class "Default")
      (node (ref "C42") (pin "2") (pinfunction "2_2") (pintype "passive"))
      (node (ref "R24") (pin "1") (pinfunction "1_1") (pintype "passive"))
    )
    (net (code "51") (name "Net-(C44-Pad2)") (class "Default")
      (node (ref "C44") (pin "2") (pinfunction "2_2") (pintype "passive"))
      (node (ref "R25") (pin "1") (pinfunction "1_1") (pintype "passive"))
    )
    (net (code "52") (name "Net-(C45-Pad2)") (class "Default")
      (node (ref "C45") (pin "2") (pinfunction "2_2") (pintype "passive"))
      (node (ref "R26") (pin "2") (pinfunction "2_2") (pintype "passive"))
    )
    (net (code "53") (name "Net-(EM1-A)") (class "Default")
      (node (ref "C10") (pin "2") (pinfunction "2_2") (pintype "passive"))
      (node (ref "EM1") (pin "1") (pinfunction "A_1") (pintype "passive"))
      (node (ref "L3") (pin "2") (pinfunction "2_2") (pintype "passive"))
    )
    (net (code "54") (name "Net-(LED1-A-Pad2)") (class "Default")
      (node (ref "LED1") (pin "2") (pinfunction "A_2") (pintype "passive"))
      (node (ref "R13") (pin "2") (pinfunction "2_2") (pintype "passive"))
    )
    (net (code "55") (name "Net-(LED1-A-Pad3)") (class "Default")
      (node (ref "LED1") (pin "3") (pinfunction "A_3") (pintype "passive"))
      (node (ref "R11") (pin "2") (pinfunction "2_2") (pintype "passive"))
    )
    (net (code "56") (name "Net-(LED2-A)") (class "Default")
      (node (ref "LED2") (pin "1") (pinfunction "A_1") (pintype "passive"))
      (node (ref "R14") (pin "2") (pinfunction "2_2") (pintype "passive"))
    )
    (net (code "57") (name "Net-(LED3-A-Pad2)") (class "Default")
      (node (ref "LED3") (pin "2") (pinfunction "A_2") (pintype "passive"))
      (node (ref "R17") (pin "2") (pinfunction "2_2") (pintype "passive"))
    )
    (net (code "58") (name "Net-(LED3-A-Pad3)") (class "Default")
      (node (ref "LED3") (pin "3") (pinfunction "A_3") (pintype "passive"))
      (node (ref "R18") (pin "2") (pinfunction "2_2") (pintype "passive"))
    )
    (net (code "59") (name "Net-(N2-D)") (class "Default")
      (node (ref "C39") (pin "1") (pinfunction "1_1") (pintype "passive"))
      (node (ref "N2") (pin "3") (pinfunction "D_3") (pintype "passive"))
      (node (ref "U9") (pin "12") (pinfunction "LDO5V_12") (pintype "passive"))
    )
    (net (code "60") (name "Net-(N2-G)") (class "Default")
      (node (ref "N2") (pin "1") (pinfunction "G_1") (pintype "passive"))
      (node (ref "R28") (pin "1") (pinfunction "1_1") (pintype "passive"))
      (node (ref "R29") (pin "2") (pinfunction "2_2") (pintype "passive"))
    )
    (net (code "61") (name "Net-(N3-D)") (class "Default")
      (node (ref "N3") (pin "3") (pinfunction "D_3") (pintype "passive"))
      (node (ref "R15") (pin "2") (pinfunction "2_2") (pintype "passive"))
    )
    (net (code "62") (name "Net-(N3-G)") (class "Default")
      (node (ref "N3") (pin "1") (pinfunction "G_1") (pintype "passive"))
      (node (ref "Q1") (pin "3") (pinfunction "C_3") (pintype "passive"))
      (node (ref "R32") (pin "2") (pinfunction "2_2") (pintype "passive"))
    )
    (net (code "63") (name "Net-(OLED1-C1N)") (class "Default")
      (node (ref "C19") (pin "1") (pinfunction "1_1") (pintype "passive"))
      (node (ref "OLED1") (pin "5") (pinfunction "C1N_5") (pintype "passive"))
    )
    (net (code "64") (name "Net-(OLED1-C1P)") (class "Default")
      (node (ref "C19") (pin "2") (pinfunction "2_2") (pintype "passive"))
      (node (ref "OLED1") (pin "4") (pinfunction "C1P_4") (pintype "passive"))
    )
    (net (code "65") (name "Net-(OLED1-C2N)") (class "Default")
      (node (ref "C18") (pin "1") (pinfunction "1_1") (pintype "passive"))
      (node (ref "OLED1") (pin "3") (pinfunction "C2N_3") (pintype "passive"))
    )
    (net (code "66") (name "Net-(OLED1-C2P)") (class "Default")
      (node (ref "C18") (pin "2") (pinfunction "2_2") (pintype "passive"))
      (node (ref "OLED1") (pin "2") (pinfunction "C2P_2") (pintype "passive"))
    )
    (net (code "67") (name "Net-(OLED1-IREF)") (class "Default")
      (node (ref "OLED1") (pin "26") (pinfunction "IREF_26") (pintype "passive"))
      (node (ref "R12") (pin "2") (pinfunction "2_2") (pintype "passive"))
    )
    (net (code "68") (name "Net-(OLED1-VCC)") (class "Default")
      (node (ref "C16") (pin "2") (pinfunction "2_2") (pintype "passive"))
      (node (ref "OLED1") (pin "28") (pinfunction "VCC_28") (pintype "passive"))
    )
    (net (code "69") (name "Net-(OLED1-VCOMH)") (class "Default")
      (node (ref "C17") (pin "2") (pinfunction "2_2") (pintype "passive"))
      (node (ref "OLED1") (pin "27") (pinfunction "VCOMH_27") (pintype "passive"))
    )
    (net (code "70") (name "Net-(Q1-B)") (class "Default")
      (node (ref "Q1") (pin "1") (pinfunction "B_1") (pintype "passive"))
      (node (ref "R30") (pin "1") (pinfunction "1_1") (pintype "passive"))
    )
    (net (code "71") (name "Net-(R5-Pad1)") (class "Default")
      (node (ref "R5") (pin "1") (pinfunction "1_1") (pintype "passive"))
      (node (ref "R6") (pin "2") (pinfunction "2_2") (pintype "passive"))
      (node (ref "U4") (pin "3") (pintype "passive"))
    )
    (net (code "72") (name "Net-(R10-Pad1)") (class "Default")
      (node (ref "R10") (pin "1") (pinfunction "1_1") (pintype "passive"))
      (node (ref "R7") (pin "2") (pinfunction "2_2") (pintype "passive"))
      (node (ref "U4") (pin "4") (pintype "passive"))
    )
    (net (code "73") (name "Net-(S1-0)") (class "Default")
      (node (ref "R2") (pin "2") (pinfunction "2_2") (pintype "passive"))
      (node (ref "S1") (pin "1") (pinfunction "0_1") (pintype "passive"))
    )
    (net (code "74") (name "Net-(S2-0)") (class "Default")
      (node (ref "R3") (pin "2") (pinfunction "2_2") (pintype "passive"))
      (node (ref "S2") (pin "1") (pinfunction "0_1") (pintype "passive"))
    )
    (net (code "75") (name "Net-(S3-0)") (class "Default")
      (node (ref "R4") (pin "2") (pinfunction "2_2") (pintype "passive"))
      (node (ref "S3") (pin "1") (pinfunction "0_1") (pintype "passive"))
    )
    (net (code "76") (name "Net-(S4-0)") (class "Default")
      (node (ref "R8") (pin "2") (pinfunction "2_2") (pintype "passive"))
      (node (ref "S4") (pin "1") (pinfunction "0_1") (pintype "passive"))
    )
    (net (code "77") (name "Net-(S5-0)") (class "Default")
      (node (ref "R9") (pin "2") (pinfunction "2_2") (pintype "passive"))
      (node (ref "S5") (pin "1") (pinfunction "0_1") (pintype "passive"))
    )
    (net (code "78") (name "Net-(U3-RXn)") (class "Default")
      (node (ref "C8") (pin "1") (pinfunction "1_1") (pintype "passive"))
      (node (ref "L2") (pin "1") (pinfunction "1_1") (pintype "passive"))
      (node (ref "U3") (pin "4") (pinfunction "RXn_4") (pintype "passive"))
    )
    (net (code "79") (name "Net-(U3-RXp)") (class "Default")
      (node (ref "C7") (pin "1") (pinfunction "1_1") (pintype "passive"))
      (node (ref "L1") (pin "2") (pinfunction "2_2") (pintype "passive"))
      (node (ref "L2") (pin "2") (pinfunction "2_2") (pintype "passive"))
      (node (ref "U3") (pin "3") (pinfunction "RXp_3") (pintype "passive"))
    )
    (net (code "80") (name "Net-(U3-TX)") (class "Default")
      (node (ref "C9") (pin "1") (pinfunction "1_1") (pintype "passive"))
      (node (ref "L6") (pin "1") (pinfunction "1_1") (pintype "passive"))
      (node (ref "U3") (pin "5") (pinfunction "TX_5") (pintype "passive"))
    )
    (net (code "81") (name "Net-(U3-XIN)") (class "Default")
      (node (ref "U3") (pin "18") (pinfunction "XIN_18") (pintype "passive"))
      (node (ref "XT1") (pin "1") (pinfunction "OSC1_1") (pintype "passive"))
    )
    (net (code "82") (name "Net-(U3-XOUT)") (class "Default")
      (node (ref "U3") (pin "17") (pinfunction "XOUT_17") (pintype "passive"))
      (node (ref "XT1") (pin "2") (pinfunction "OSC2_2") (pintype "passive"))
    )
    (net (code "83") (name "Net-(U5-PROG)") (class "Default")
      (node (ref "R19") (pin "2") (pinfunction "2_2") (pintype "passive"))
      (node (ref "U5") (pin "2") (pinfunction "PROG_2") (pintype "passive"))
    )
    (net (code "84") (name "Net-(U5-~{CHRG})") (class "Default")
      (node (ref "R18") (pin "1") (pinfunction "1_1") (pintype "passive"))
      (node (ref "U5") (pin "7") (pinfunction "~{CHRG}_7") (pintype "passive"))
    )
    (net (code "85") (name "Net-(U5-~{STDBY})") (class "Default")
      (node (ref "R17") (pin "1") (pinfunction "1_1") (pintype "passive"))
      (node (ref "U5") (pin "6") (pinfunction "~{STDBY}_6") (pintype "passive"))
    )
    (net (code "86") (name "Net-(U6-NRST)") (class "Default")
      (node (ref "C35") (pin "2") (pinfunction "2_2") (pintype "passive"))
      (node (ref "R21") (pin "1") (pinfunction "1_1") (pintype "passive"))
      (node (ref "U6") (pin "7") (pinfunction "NRST_7") (pintype "bidirectional"))
    )
    (net (code "87") (name "Net-(U6-OSC_IN)") (class "Default")
      (node (ref "C36") (pin "1") (pinfunction "1_1") (pintype "passive"))
      (node (ref "U6") (pin "5") (pinfunction "OSC_IN_5") (pintype "input"))
      (node (ref "Y1") (pin "2") (pinfunction "OSC2_2") (pintype "passive"))
    )
    (net (code "88") (name "Net-(U6-OSC_OUT)") (class "Default")
      (node (ref "C40") (pin "1") (pinfunction "1_1") (pintype "passive"))
      (node (ref "U6") (pin "6") (pinfunction "OSC_OUT_6") (pintype "output"))
      (node (ref "Y1") (pin "1") (pinfunction "OSC1_1") (pintype "passive"))
    )
    (net (code "89") (name "Net-(U6-PA13{slash}JTMS{slash}SWDIO)") (class "Default")
      (node (ref "P5") (pin "3") (pinfunction "3_3") (pintype "passive"))
      (node (ref "U6") (pin "34") (pinfunction "PA13/JTMS/SWDIO_34") (pintype "bidirectional"))
    )
    (net (code "90") (name "Net-(U6-PA14{slash}JTCK{slash}SWCLK)") (class "Default")
      (node (ref "P5") (pin "2") (pinfunction "2_2") (pintype "passive"))
      (node (ref "U6") (pin "37") (pinfunction "PA14/JTCK/SWCLK_37") (pintype "bidirectional"))
    )
    (net (code "91") (name "Net-(U7-BYP{slash}ADJ)") (class "Default")
      (node (ref "C29") (pin "2") (pinfunction "2_2") (pintype "passive"))
      (node (ref "U7") (pin "4") (pinfunction "BYP/ADJ_4") (pintype "passive"))
    )
    (net (code "92") (name "Net-(U7-EN)") (class "Default")
      (node (ref "R20") (pin "1") (pinfunction "1_1") (pintype "passive"))
      (node (ref "U7") (pin "3") (pinfunction "EN_3") (pintype "passive"))
    )
    (net (code "93") (name "Net-(U9-GPIOA6)") (class "Default")
      (node (ref "C37") (pin "1") (pinfunction "1_1") (pintype "passive"))
      (node (ref "U9") (pin "7") (pinfunction "GPIOA6_7") (pintype "passive"))
    )
    (net (code "94") (name "Net-(U9-VDDIO)") (class "Default")
      (node (ref "C38") (pin "1") (pinfunction "1_1") (pintype "passive"))
      (node (ref "U9") (pin "11") (pinfunction "VDDIO_11") (pintype "passive"))
    )
    (net (code "95") (name "Net-(U10-BYP)") (class "Default")
      (node (ref "C41") (pin "2") (pinfunction "2_2") (pintype "passive"))
      (node (ref "U10") (pin "2") (pinfunction "BYP_2") (pintype "passive"))
      (node (ref "U10") (pin "3") (pinfunction "IN+_3") (pintype "passive"))
    )
    (net (code "96") (name "Net-(U10-IN-)") (class "Default")
      (node (ref "R23") (pin "1") (pinfunction "1_1") (pintype "passive"))
      (node (ref "R26") (pin "1") (pinfunction "1_1") (pintype "passive"))
      (node (ref "U10") (pin "4") (pinfunction "IN-_4") (pintype "passive"))
    )
    (net (code "97") (name "V33") (class "Default")
      (node (ref "U8") (pin "3") (pinfunction "WP/_3") (pintype "passive"))
    )
    (net (code "98") (name "VCC") (class "Default")
      (node (ref "C27") (pin "2") (pinfunction "2_2") (pintype "passive"))
      (node (ref "LED3") (pin "1") (pinfunction "K_1") (pintype "passive"))
      (node (ref "P3") (pin "2") (pinfunction "2_2") (pintype "passive"))
      (node (ref "U5") (pin "4") (pinfunction "VCC_4") (pintype "passive"))
      (node (ref "U5") (pin "8") (pinfunction "CE_8") (pintype "passive"))
      (node (ref "USB") (pin "1") (pinfunction "VCC_1") (pintype "passive"))
    )
    (net (code "99") (name "VCC3.3V") (class "Default")
      (node (ref "C13") (pin "1") (pinfunction "1_1") (pintype "passive"))
      (node (ref "C14") (pin "1") (pinfunction "1_1") (pintype "passive"))
      (node (ref "C15") (pin "2") (pinfunction "2_2") (pintype "passive"))
      (node (ref "C20") (pin "2") (pinfunction "2_2") (pintype "passive"))
      (node (ref "C21") (pin "2") (pinfunction "2_2") (pintype "passive"))
      (node (ref "C30") (pin "2") (pinfunction "2_2") (pintype "passive"))
      (node (ref "C5") (pin "1") (pinfunction "1_1") (pintype "passive"))
      (node (ref "C6") (pin "1") (pinfunction "1_1") (pintype "passive"))
      (node (ref "L6") (pin "2") (pinfunction "2_2") (pintype "passive"))
      (node (ref "N2") (pin "2") (pinfunction "S_2") (pintype "passive"))
      (node (ref "OLED1") (pin "6") (pinfunction "VBAT_6") (pintype "passive"))
      (node (ref "OLED1") (pin "9") (pinfunction "VDD_9") (pintype "passive"))
      (node (ref "P1") (pin "3") (pinfunction "3_3") (pintype "passive"))
      (node (ref "P2") (pin "4") (pinfunction "4_4") (pintype "passive"))
      (node (ref "R29") (pin "1") (pinfunction "1_1") (pintype "passive"))
      (node (ref "R31") (pin "2") (pinfunction "2_2") (pintype "passive"))
      (node (ref "U1") (pin "1") (pinfunction "REST_1") (pintype "passive"))
      (node (ref "U3") (pin "7") (pinfunction "VDD_7") (pintype "passive"))
      (node (ref "U3") (pin "8") (pinfunction "VDD_8") (pintype "passive"))
      (node (ref "U4") (pin "5") (pintype "passive"))
      (node (ref "U7") (pin "5") (pinfunction "OUT_5") (pintype "passive"))
      (node (ref "U8") (pin "7") (pinfunction "HOLD/_7") (pintype "passive"))
      (node (ref "U8") (pin "8") (pinfunction "VCC_8") (pintype "passive"))
    )
    (net (code "100") (name "VCC_BAT") (class "Default")
      (node (ref "C2") (pin "2") (pinfunction "2_2") (pintype "passive"))
      (node (ref "C22") (pin "2") (pinfunction "2_2") (pintype "passive"))
      (node (ref "C23") (pin "2") (pinfunction "2_2") (pintype "passive"))
      (node (ref "C26") (pin "2") (pinfunction "2_2") (pintype "passive"))
      (node (ref "C28") (pin "2") (pinfunction "2_2") (pintype "passive"))
      (node (ref "C3") (pin "2") (pinfunction "2_2") (pintype "passive"))
      (node (ref "C4") (pin "2") (pinfunction "2_2") (pintype "passive"))
      (node (ref "C43") (pin "2") (pinfunction "2_2") (pintype "passive"))
      (node (ref "N3") (pin "2") (pinfunction "S_2") (pintype "passive"))
      (node (ref "P4") (pin "1") (pinfunction "1_1") (pintype "passive"))
      (node (ref "R27") (pin "2") (pinfunction "2_2") (pintype "passive"))
      (node (ref "R32") (pin "1") (pinfunction "1_1") (pintype "passive"))
      (node (ref "U10") (pin "6") (pinfunction "VDD_6") (pintype "passive"))
      (node (ref "U2") (pin "6") (pinfunction "VCC_6") (pintype "passive"))
      (node (ref "U5") (pin "5") (pinfunction "BAT_5") (pintype "passive"))
      (node (ref "U7") (pin "1") (pinfunction "IN_1") (pintype "passive"))
      (node (ref "VR1") (pin "3") (pinfunction "Vin_3") (pintype "passive"))
    )
    (net (code "101") (name "VDD3.3") (class "Default")
      (node (ref "C1") (pin "1") (pinfunction "1_1") (pintype "passive"))
      (node (ref "C24") (pin "2") (pinfunction "2_2") (pintype "passive"))
      (node (ref "C25") (pin "2") (pinfunction "2_2") (pintype "passive"))
      (node (ref "C31") (pin "2") (pinfunction "2_2") (pintype "passive"))
      (node (ref "C32") (pin "2") (pinfunction "2_2") (pintype "passive"))
      (node (ref "C33") (pin "2") (pinfunction "2_2") (pintype "passive"))
      (node (ref "C34") (pin "2") (pinfunction "2_2") (pintype "passive"))
      (node (ref "P5") (pin "4") (pinfunction "4_4") (pintype "passive"))
      (node (ref "R1") (pin "2") (pinfunction "2_2") (pintype "passive"))
      (node (ref "R21") (pin "2") (pinfunction "2_2") (pintype "passive"))
      (node (ref "U6") (pin "24") (pinfunction "VDD_1_24") (pintype "power_in"))
      (node (ref "U6") (pin "36") (pinfunction "VDD_2_36") (pintype "power_in"))
      (node (ref "U6") (pin "48") (pinfunction "VDD_3_48") (pintype "power_in"))
      (node (ref "U6") (pin "9") (pinfunction "VDDA_9") (pintype "power_in"))
      (node (ref "VR1") (pin "2") (pinfunction "Vout_2") (pintype "passive"))
    )
    (net (code "102") (name "unconnected-(OLED1-D2-Pad20)") (class "Default")
      (node (ref "OLED1") (pin "20") (pinfunction "D2_20") (pintype "passive"))
    )
    (net (code "103") (name "unconnected-(OLED1-NC(VBREF)-Pad7)") (class "Default")
      (node (ref "OLED1") (pin "7") (pinfunction "NC(VBREF)_7") (pintype "passive"))
    )
    (net (code "104") (name "unconnected-(OLED1-NC(VSS)-Pad1)") (class "Default")
      (node (ref "OLED1") (pin "1") (pinfunction "NC(VSS)_1") (pintype "passive"))
    )
    (net (code "105") (name "unconnected-(OLED1-NC(VSS)-Pad30)") (class "Default")
      (node (ref "OLED1") (pin "30") (pinfunction "NC(VSS)_30") (pintype "passive"))
    )
    (net (code "106") (name "unconnected-(U3-GND-Pad9)") (class "Default")
      (node (ref "U3") (pin "9") (pinfunction "GND_9") (pintype "passive"))
    )
    (net (code "107") (name "unconnected-(U3-GPIO1-Pad11)") (class "Default")
      (node (ref "U3") (pin "11") (pinfunction "GPIO1_11") (pintype "passive"))
    )
    (net (code "108") (name "unconnected-(U3-GPIO2-Pad19)") (class "Default")
      (node (ref "U3") (pin "19") (pinfunction "GPIO2_19") (pintype "passive"))
    )
    (net (code "109") (name "unconnected-(U3-GPIO3-Pad20)") (class "Default")
      (node (ref "U3") (pin "20") (pinfunction "GPIO3_20") (pintype "passive"))
    )
    (net (code "110") (name "unconnected-(U6-BOOT0-Pad44)") (class "Default")
      (node (ref "U6") (pin "44") (pinfunction "BOOT0_44") (pintype "input"))
    )
    (net (code "111") (name "unconnected-(U6-PA15{slash}JTDI-Pad38)") (class "Default")
      (node (ref "U6") (pin "38") (pinfunction "PA15/JTDI_38") (pintype "bidirectional"))
    )
    (net (code "112") (name "unconnected-(U6-VBAT-Pad1)") (class "Default")
      (node (ref "U6") (pin "1") (pinfunction "VBAT_1") (pintype "power_in"))
    )
    (net (code "113") (name "unconnected-(U9-GPIOA3-Pad4)") (class "Default")
      (node (ref "U9") (pin "4") (pinfunction "GPIOA3_4") (pintype "passive"))
    )
  )
)
